# Sheet_FS872.net
KiCad netlist of a schematic drawn in Altium Designer
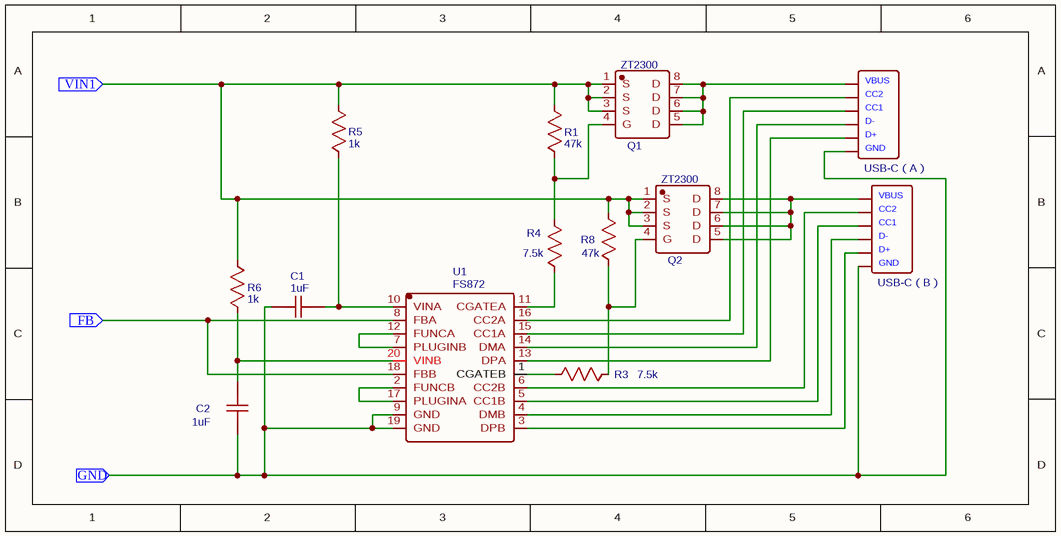
[diagram p0: Sheet_FS872.schdoc]

(export (version "E")
  (design (tool "Eeschema 10.0.6"))
  (components
    (comp (ref "C1")
      (value "1uF")
      (footprint "C0603")
      (fields (field (name "CONTRIBUTOR") "LCEDA_Lib"))
      (libsource (lib "altium-import") (part "root_0_0.1u_"))
    )
    (comp (ref "C2")
      (value "1uF")
      (footprint "C0603")
      (fields (field (name "CONTRIBUTOR") "LCEDA_Lib"))
      (libsource (lib "altium-import") (part "root_1_0.1u_"))
    )
    (comp (ref "Q1")
      (value "ZT2300")
      (footprint "DFN3X3-8L")
      (fields
        (field (name "MANUFACTURER") "VBsemi Elec")
        (field (name "MANUFACTURER PART") "NCE3035G")
        (field (name "CONTRIBUTOR") "LCSC")
      )
      (libsource (lib "altium-import") (part "root_0_ZT2300_"))
    )
    (comp (ref "Q2")
      (value "ZT2300")
      (footprint "DFN3X3-8L")
      (fields
        (field (name "MANUFACTURER") "VBsemi Elec")
        (field (name "MANUFACTURER PART") "NCE3035G")
        (field (name "CONTRIBUTOR") "LCSC")
      )
      (libsource (lib "altium-import") (part "root_0_ZT2300_"))
    )
    (comp (ref "R1")
      (value "47k")
      (footprint "R0603")
      (fields (field (name "CONTRIBUTOR") "LCEDA_Lib"))
      (libsource (lib "altium-import") (part "root_1_47k_"))
    )
    (comp (ref "R3")
      (value "7.5k")
      (footprint "R0603")
      (fields (field (name "CONTRIBUTOR") "LCEDA_Lib"))
      (libsource (lib "altium-import") (part "root_0_7.5k_"))
    )
    (comp (ref "R4")
      (value "7.5k")
      (footprint "R0603")
      (fields (field (name "CONTRIBUTOR") "LCEDA_Lib"))
      (libsource (lib "altium-import") (part "root_1_7.5k_"))
    )
    (comp (ref "R5")
      (value "1k")
      (footprint "R1206")
      (fields (field (name "CONTRIBUTOR") "LCEDA_Lib"))
      (libsource (lib "altium-import") (part "root_1_1k_"))
    )
    (comp (ref "R6")
      (value "1k")
      (footprint "R1206")
      (fields (field (name "CONTRIBUTOR") "LCEDA_Lib"))
      (libsource (lib "altium-import") (part "root_1_1k_"))
    )
    (comp (ref "R8")
      (value "47k")
      (footprint "R0603")
      (fields (field (name "CONTRIBUTOR") "LCEDA_Lib"))
      (libsource (lib "altium-import") (part "root_1_47k_"))
    )
    (comp (ref "U1")
      (value "FS872")
      (footprint "ETSSOP20_L6.5-W4.4-P0.65-LS6.4-BL")
      (fields
        (field (name "MANUFACTURER") "TI(德州仪器)")
        (field (name "MANUFACTURER PART") "PCF8574APWR")
        (field (name "CONTRIBUTOR") "LCSC")
      )
      (libsource (lib "altium-import") (part "root_0_FS8626_"))
    )
    (comp (ref "U2")
      (value "USB-C（B）")
      (footprint "FCQFN-15L_L3.0-W3.0-P0.50-BL_SCT63140FMAR")
      (fields
        (field (name "MANUFACTURER") "SCT")
        (field (name "MANUFACTURER PART") "SCT63140FMAR")
        (field (name "CONTRIBUTOR") "TaoPatrick")
      )
      (libsource (lib "altium-import") (part "root_0_USB-C（B）_"))
    )
    (comp (ref "U3")
      (value "USB-C（A）")
      (footprint "FCQFN-15L_L3.0-W3.0-P0.50-BL_SCT63140FMAR")
      (fields
        (field (name "MANUFACTURER") "SCT")
        (field (name "MANUFACTURER PART") "SCT63140FMAR")
        (field (name "CONTRIBUTOR") "TaoPatrick")
      )
      (libsource (lib "altium-import") (part "root_0_USB-C（A）_"))
    )
  )
  (nets
    (net (code "1") (name "/FB") (class "Default")
      (node (ref "U1") (pin "18") (pinfunction "FBB_18") (pintype "passive"))
      (node (ref "U1") (pin "8") (pinfunction "FBA_8") (pintype "passive"))
    )
    (net (code "2") (name "/GND") (class "Default")
      (node (ref "C1") (pin "1") (pinfunction "1_1") (pintype "passive"))
      (node (ref "C2") (pin "1") (pinfunction "1_1") (pintype "passive"))
      (node (ref "U1") (pin "19") (pinfunction "GND_19") (pintype "passive"))
      (node (ref "U1") (pin "9") (pinfunction "GND_9") (pintype "passive"))
    )
    (net (code "3") (name "/VIN1") (class "Default")
      (node (ref "Q1") (pin "1") (pinfunction "S_1") (pintype "passive"))
      (node (ref "Q1") (pin "2") (pinfunction "S_2") (pintype "passive"))
      (node (ref "Q1") (pin "3") (pinfunction "S_3") (pintype "passive"))
      (node (ref "Q2") (pin "1") (pinfunction "S_1") (pintype "passive"))
      (node (ref "Q2") (pin "2") (pinfunction "S_2") (pintype "passive"))
      (node (ref "Q2") (pin "3") (pinfunction "S_3") (pintype "passive"))
      (node (ref "R1") (pin "2") (pinfunction "2_2") (pintype "passive"))
      (node (ref "R5") (pin "2") (pinfunction "2_2") (pintype "passive"))
      (node (ref "R6") (pin "2") (pinfunction "2_2") (pintype "passive"))
      (node (ref "R8") (pin "2") (pinfunction "2_2") (pintype "passive"))
    )
    (net (code "4") (name "Net-(Q1-D-Pad5)") (class "Default")
      (node (ref "Q1") (pin "5") (pinfunction "D_5") (pintype "passive"))
      (node (ref "Q1") (pin "6") (pinfunction "D_6") (pintype "passive"))
      (node (ref "Q1") (pin "7") (pinfunction "D_7") (pintype "passive"))
      (node (ref "Q1") (pin "8") (pinfunction "D_8") (pintype "passive"))
    )
    (net (code "5") (name "Net-(Q1-G)") (class "Default")
      (node (ref "Q1") (pin "4") (pinfunction "G_4") (pintype "passive"))
      (node (ref "R1") (pin "1") (pinfunction "1_1") (pintype "passive"))
      (node (ref "R4") (pin "2") (pinfunction "2_2") (pintype "passive"))
    )
    (net (code "6") (name "Net-(Q2-D-Pad5)") (class "Default")
      (node (ref "Q2") (pin "5") (pinfunction "D_5") (pintype "passive"))
      (node (ref "Q2") (pin "6") (pinfunction "D_6") (pintype "passive"))
      (node (ref "Q2") (pin "7") (pinfunction "D_7") (pintype "passive"))
      (node (ref "Q2") (pin "8") (pinfunction "D_8") (pintype "passive"))
    )
    (net (code "7") (name "Net-(Q2-G)") (class "Default")
      (node (ref "Q2") (pin "4") (pinfunction "G_4") (pintype "passive"))
      (node (ref "R3") (pin "2") (pinfunction "2_2") (pintype "passive"))
      (node (ref "R8") (pin "1") (pinfunction "1_1") (pintype "passive"))
    )
    (net (code "8") (name "Net-(U1-CGATEA)") (class "Default")
      (node (ref "R4") (pin "1") (pinfunction "1_1") (pintype "passive"))
      (node (ref "U1") (pin "11") (pinfunction "CGATEA_11") (pintype "passive"))
    )
    (net (code "9") (name "Net-(U1-CGATEB)") (class "Default")
      (node (ref "R3") (pin "1") (pinfunction "1_1") (pintype "passive"))
      (node (ref "U1") (pin "1") (pinfunction "CGATEB_1") (pintype "passive"))
    )
    (net (code "10") (name "Net-(U1-FUNCA)") (class "Default")
      (node (ref "U1") (pin "12") (pinfunction "FUNCA_12") (pintype "passive"))
      (node (ref "U1") (pin "7") (pinfunction "PLUGINB_7") (pintype "passive"))
    )
    (net (code "11") (name "Net-(U1-FUNCB)") (class "Default")
      (node (ref "U1") (pin "17") (pinfunction "PLUGINA_17") (pintype "passive"))
      (node (ref "U1") (pin "2") (pinfunction "FUNCB_2") (pintype "passive"))
    )
    (net (code "12") (name "Net-(U1-VINA)") (class "Default")
      (node (ref "C1") (pin "2") (pinfunction "2_2") (pintype "passive"))
      (node (ref "R5") (pin "1") (pinfunction "1_1") (pintype "passive"))
      (node (ref "U1") (pin "10") (pinfunction "VINA_10") (pintype "passive"))
    )
    (net (code "13") (name "Net-(U1-VINB)") (class "Default")
      (node (ref "C2") (pin "2") (pinfunction "2_2") (pintype "passive"))
      (node (ref "R6") (pin "1") (pinfunction "1_1") (pintype "passive"))
      (node (ref "U1") (pin "20") (pinfunction "VINB_20") (pintype "passive"))
    )
    (net (code "14") (name "unconnected-(U1-CC1A-Pad15)") (class "Default")
      (node (ref "U1") (pin "15") (pinfunction "CC1A_15") (pintype "passive"))
    )
    (net (code "15") (name "unconnected-(U1-CC1B-Pad5)") (class "Default")
      (node (ref "U1") (pin "5") (pinfunction "CC1B_5") (pintype "passive"))
    )
    (net (code "16") (name "unconnected-(U1-CC2A-Pad16)") (class "Default")
      (node (ref "U1") (pin "16") (pinfunction "CC2A_16") (pintype "passive"))
    )
    (net (code "17") (name "unconnected-(U1-CC2B-Pad6)") (class "Default")
      (node (ref "U1") (pin "6") (pinfunction "CC2B_6") (pintype "passive"))
    )
    (net (code "18") (name "unconnected-(U1-DMA-Pad14)") (class "Default")
      (node (ref "U1") (pin "14") (pinfunction "DMA_14") (pintype "passive"))
    )
    (net (code "19") (name "unconnected-(U1-DMB-Pad4)") (class "Default")
      (node (ref "U1") (pin "4") (pinfunction "DMB_4") (pintype "passive"))
    )
    (net (code "20") (name "unconnected-(U1-DPA-Pad13)") (class "Default")
      (node (ref "U1") (pin "13") (pinfunction "DPA_13") (pintype "passive"))
    )
    (net (code "21") (name "unconnected-(U1-DPB-Pad3)") (class "Default")
      (node (ref "U1") (pin "3") (pinfunction "DPB_3") (pintype "passive"))
    )
    (net (code "22") (name "unconnected-(U2-SHELD-Pad2)") (class "Default")
      (node (ref "U2") (pin "2") (pinfunction "SHELD_2") (pintype "passive"))
    )
    (net (code "23") (name "unconnected-(U2-SHELD-Pad3)") (class "Default")
      (node (ref "U2") (pin "3") (pinfunction "SHELD_3") (pintype "passive"))
    )
    (net (code "24") (name "unconnected-(U2-SHELD-Pad4)") (class "Default")
      (node (ref "U2") (pin "4") (pinfunction "SHELD_4") (pintype "passive"))
    )
    (net (code "25") (name "unconnected-(U2-SHELD-Pad5)") (class "Default")
      (node (ref "U2") (pin "5") (pinfunction "SHELD_5") (pintype "passive"))
    )
    (net (code "26") (name "unconnected-(U2-SHELD-Pad5)_1") (class "Default")
      (node (ref "U2") (pin "5") (pinfunction "SHELD_5") (pintype "passive"))
    )
    (net (code "27") (name "unconnected-(U2-SHELD-Pad6)") (class "Default")
      (node (ref "U2") (pin "6") (pinfunction "SHELD_6") (pintype "passive"))
    )
    (net (code "28") (name "unconnected-(U3-SHELD-Pad2)") (class "Default")
      (node (ref "U3") (pin "2") (pinfunction "SHELD_2") (pintype "passive"))
    )
    (net (code "29") (name "unconnected-(U3-SHELD-Pad3)") (class "Default")
      (node (ref "U3") (pin "3") (pinfunction "SHELD_3") (pintype "passive"))
    )
    (net (code "30") (name "unconnected-(U3-SHELD-Pad4)") (class "Default")
      (node (ref "U3") (pin "4") (pinfunction "SHELD_4") (pintype "passive"))
    )
    (net (code "31") (name "unconnected-(U3-SHELD-Pad5)") (class "Default")
      (node (ref "U3") (pin "5") (pinfunction "SHELD_5") (pintype "passive"))
    )
    (net (code "32") (name "unconnected-(U3-SHELD-Pad5)_1") (class "Default")
      (node (ref "U3") (pin "5") (pinfunction "SHELD_5") (pintype "passive"))
    )
    (net (code "33") (name "unconnected-(U3-SHELD-Pad6)") (class "Default")
      (node (ref "U3") (pin "6") (pinfunction "SHELD_6") (pintype "passive"))
    )
  )
)
